# design.net
KiCad netlist of a schematic drawn in Altium Designer
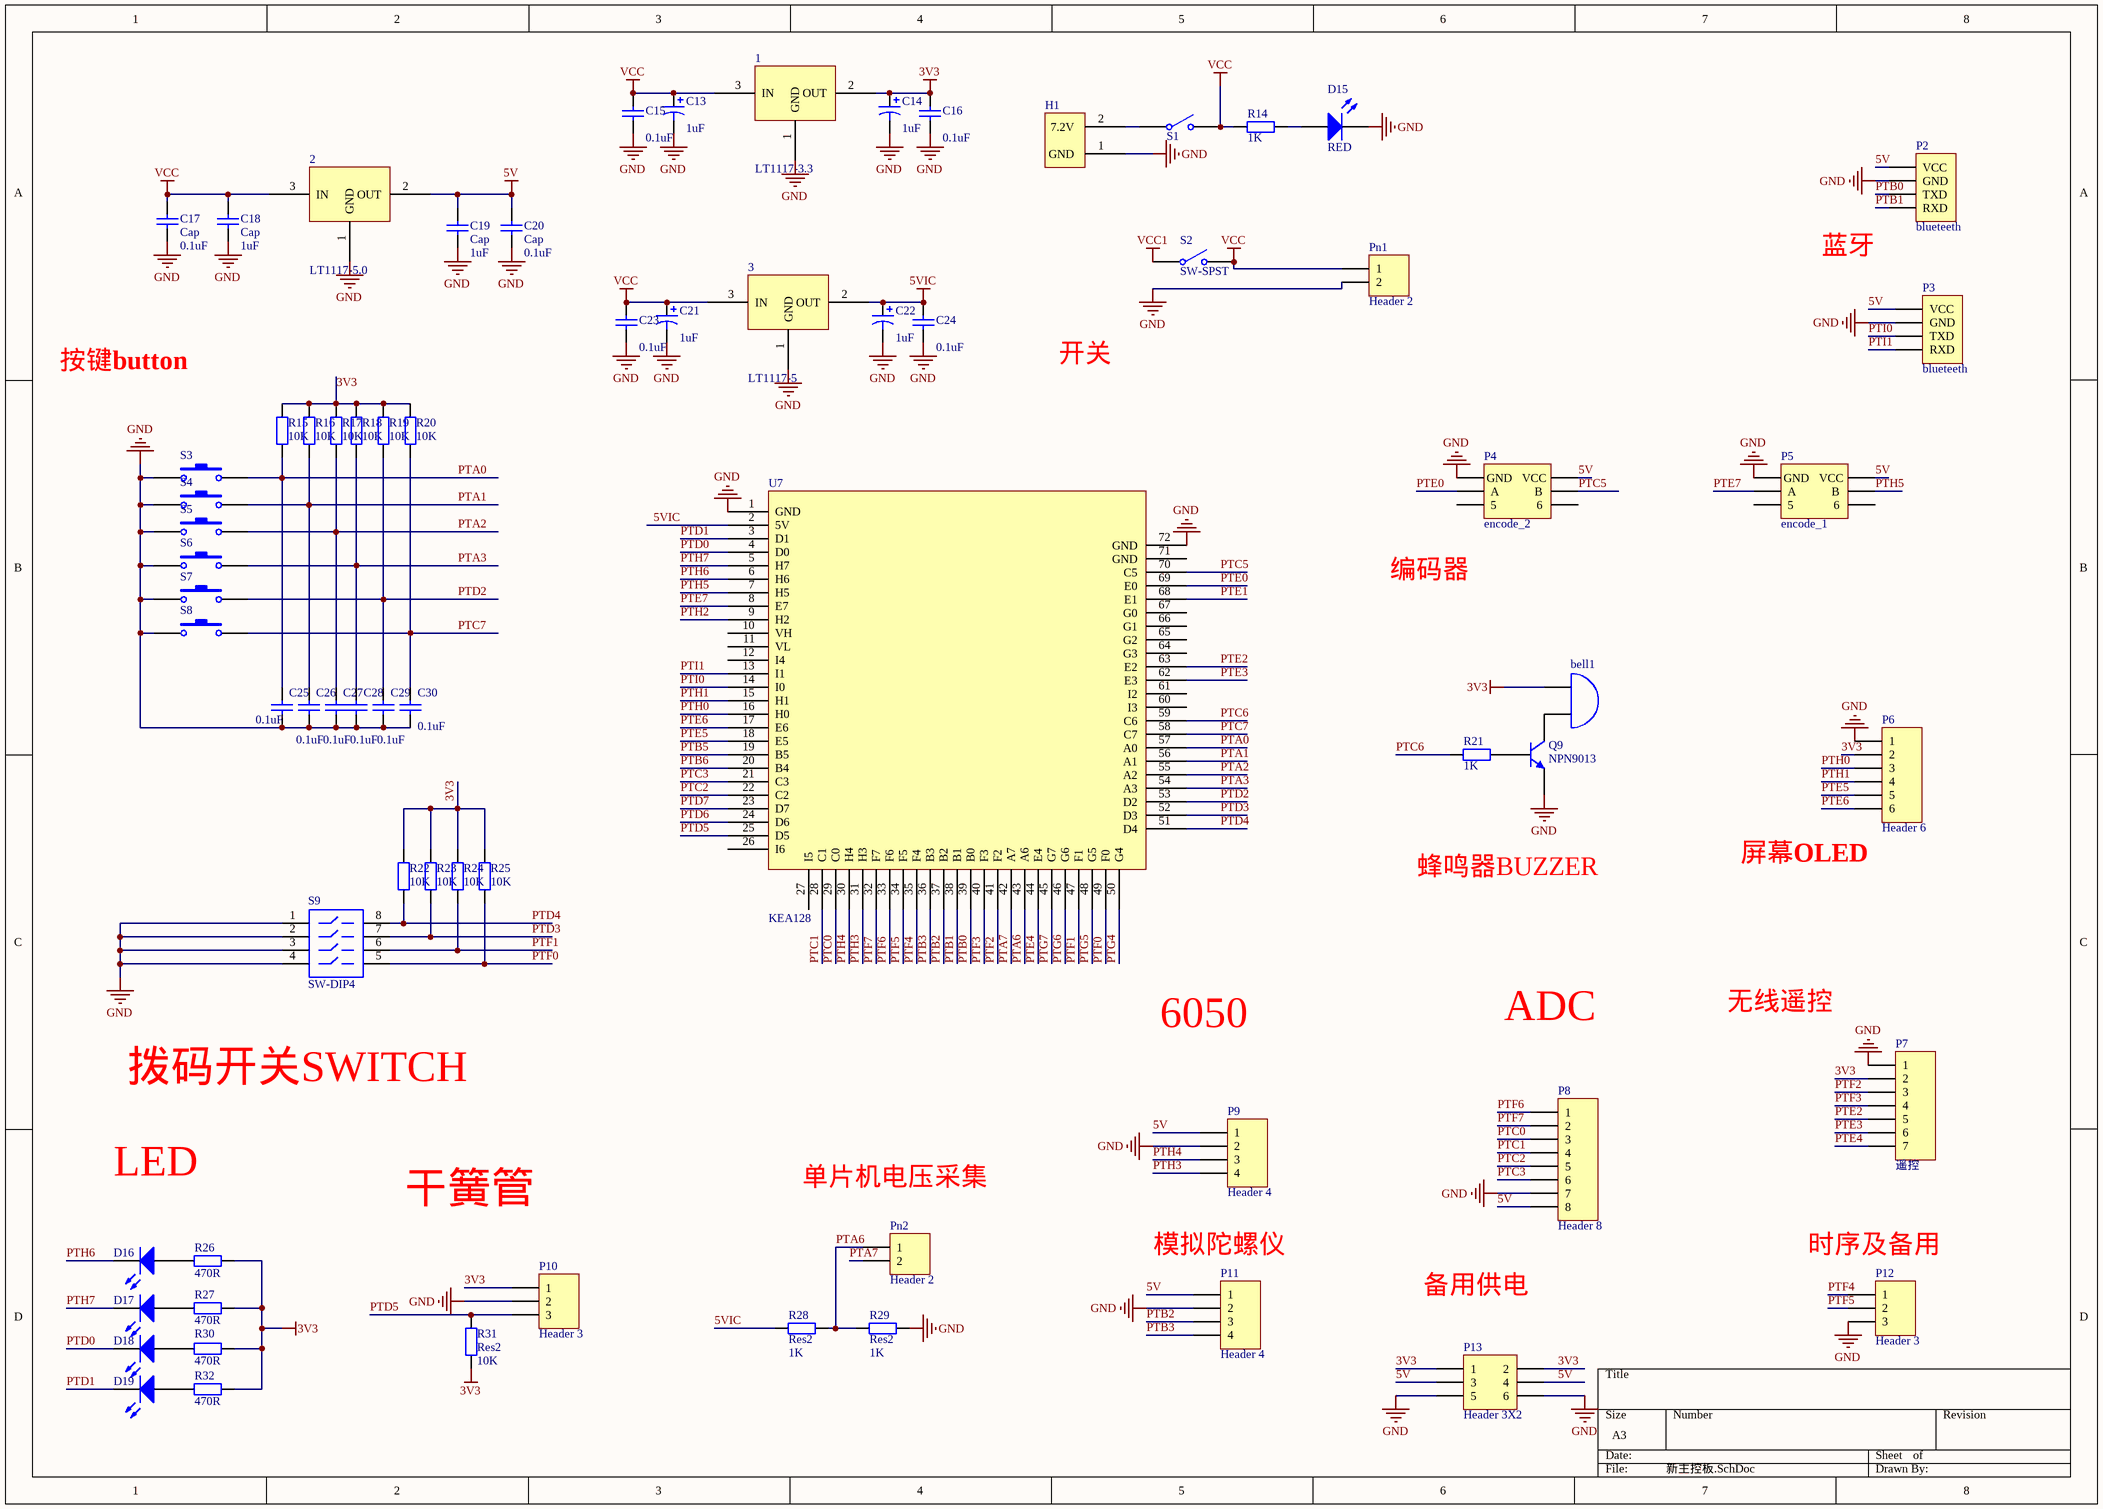
[diagram p0: 新主控板.SchDoc]

(export (version "E")
  (design (tool "Eeschema 10.0.6"))
  (components
    (comp (ref "1")
      (value "LT1117-3.3")
      (footprint "WH:1117")
      (libsource (lib "红牛板Schlib") (part "LT1117-3.3"))
    )
    (comp (ref "2") (value "LT1117-5.0") (footprint "WH:1117") (libsource (lib "新主控板") (part "LT1117-3.3")))
    (comp (ref "3")
      (value "LT1117-5")
      (footprint "WH:1117")
      (libsource (lib "红牛板Schlib") (part "LT1117-3.3"))
    )
    (comp (ref "bell1")
      (value "Bell")
      (footprint "470uF")
      (description "Electrical Bell")
      (fields (field (name "PUBLISHER") "Altium Limited"))
      (libsource (lib "Miscellaneous Devices") (part "Bell"))
    )
    (comp (ref "C13")
      (value "1uF")
      (footprint "0805(2012)")
      (description "Polarized Capacitor (Radial)")
      (fields (field (name "Comment") "Cap Pol1") (field (name "PUBLISHER") "Altium Limited"))
      (libsource (lib "Miscellaneous Devices") (part "Cap Pol1"))
    )
    (comp (ref "C14")
      (value "1uF")
      (footprint "0805(2012)")
      (description "Polarized Capacitor (Radial)")
      (fields (field (name "Comment") "Cap Pol1") (field (name "PUBLISHER") "Altium Limited"))
      (libsource (lib "Miscellaneous Devices") (part "Cap Pol1"))
    )
    (comp (ref "C15")
      (value "0.1uF")
      (footprint "0805(2012)")
      (description "Capacitor")
      (fields (field (name "Comment") "Cap") (field (name "PUBLISHER") "Altium Limited"))
      (libsource (lib "Miscellaneous Devices") (part "Cap"))
    )
    (comp (ref "C16")
      (value "0.1uF")
      (footprint "0805(2012)")
      (description "Capacitor")
      (fields (field (name "Comment") "Cap") (field (name "PUBLISHER") "Altium Limited"))
      (libsource (lib "Miscellaneous Devices") (part "Cap"))
    )
    (comp (ref "C17")
      (value "Cap")
      (footprint "0805(2012)")
      (description "Capacitor")
      (fields (field (name "ALTIUM_VALUE") "0.1uF") (field (name "PUBLISHER") "Altium Limited"))
      (libsource (lib "Miscellaneous Devices") (part "Cap"))
    )
    (comp (ref "C18")
      (value "Cap")
      (footprint "0805(2012)")
      (description "Capacitor")
      (fields (field (name "ALTIUM_VALUE") "1uF") (field (name "PUBLISHER") "Altium Limited"))
      (libsource (lib "Miscellaneous Devices") (part "Cap"))
    )
    (comp (ref "C19")
      (value "Cap")
      (footprint "0805(2012)")
      (description "Capacitor")
      (fields (field (name "ALTIUM_VALUE") "1uF") (field (name "PUBLISHER") "Altium Limited"))
      (libsource (lib "Miscellaneous Devices") (part "Cap"))
    )
    (comp (ref "C20")
      (value "Cap")
      (footprint "0805(2012)")
      (description "Capacitor")
      (fields (field (name "ALTIUM_VALUE") "0.1uF") (field (name "PUBLISHER") "Altium Limited"))
      (libsource (lib "Miscellaneous Devices") (part "Cap"))
    )
    (comp (ref "C21")
      (value "1uF")
      (footprint "0805(2012)")
      (description "Polarized Capacitor (Radial)")
      (fields (field (name "Comment") "Cap Pol1") (field (name "PUBLISHER") "Altium Limited"))
      (libsource (lib "Miscellaneous Devices") (part "Cap Pol1"))
    )
    (comp (ref "C22")
      (value "1uF")
      (footprint "0805(2012)")
      (description "Polarized Capacitor (Radial)")
      (fields (field (name "Comment") "Cap Pol1") (field (name "PUBLISHER") "Altium Limited"))
      (libsource (lib "Miscellaneous Devices") (part "Cap Pol1"))
    )
    (comp (ref "C23")
      (value "0.1uF")
      (footprint "0805(2012)")
      (description "Capacitor")
      (fields (field (name "Comment") "Cap") (field (name "PUBLISHER") "Altium Limited"))
      (libsource (lib "Miscellaneous Devices") (part "Cap"))
    )
    (comp (ref "C24")
      (value "0.1uF")
      (footprint "0805(2012)")
      (description "Capacitor")
      (fields (field (name "Comment") "Cap") (field (name "PUBLISHER") "Altium Limited"))
      (libsource (lib "Miscellaneous Devices") (part "Cap"))
    )
    (comp (ref "C25")
      (value "0.1uF")
      (footprint "0805(2012)")
      (description "Capacitor")
      (fields (field (name "Comment") "Cap") (field (name "PUBLISHER") "Altium Limited"))
      (libsource (lib "Miscellaneous Devices") (part "Cap"))
    )
    (comp (ref "C26")
      (value "0.1uF")
      (footprint "0805(2012)")
      (description "Capacitor")
      (fields (field (name "Comment") "Cap") (field (name "PUBLISHER") "Altium Limited"))
      (libsource (lib "Miscellaneous Devices") (part "Cap"))
    )
    (comp (ref "C27")
      (value "0.1uF")
      (footprint "0805(2012)")
      (description "Capacitor")
      (fields (field (name "Comment") "Cap") (field (name "PUBLISHER") "Altium Limited"))
      (libsource (lib "Miscellaneous Devices") (part "Cap"))
    )
    (comp (ref "C28")
      (value "0.1uF")
      (footprint "0805(2012)")
      (description "Capacitor")
      (fields (field (name "Comment") "Cap") (field (name "PUBLISHER") "Altium Limited"))
      (libsource (lib "Miscellaneous Devices") (part "Cap"))
    )
    (comp (ref "C29")
      (value "0.1uF")
      (footprint "0805(2012)")
      (description "Capacitor")
      (fields (field (name "Comment") "Cap") (field (name "PUBLISHER") "Altium Limited"))
      (libsource (lib "Miscellaneous Devices") (part "Cap"))
    )
    (comp (ref "C30")
      (value "0.1uF")
      (footprint "0805(2012)")
      (description "Capacitor")
      (fields (field (name "Comment") "Cap") (field (name "PUBLISHER") "Altium Limited"))
      (libsource (lib "Miscellaneous Devices") (part "Cap"))
    )
    (comp (ref "D15")
      (value "RED")
      (footprint "0805LED")
      (description "Typical RED, GREEN, YELLOW, AMBER GaAs LED")
      (fields (field (name "PUBLISHER") "Altium Limited"))
      (libsource (lib "MOS motor driving module ") (part "LED2"))
    )
    (comp (ref "D16")
      (value "LED0")
      (footprint "0805LED")
      (description "Typical INFRARED GaAs LED")
      (fields (field (name "PUBLISHER") "Altium Limited"))
      (libsource (lib "Miscellaneous Devices") (part "LED0"))
    )
    (comp (ref "D17")
      (value "LED0")
      (footprint "0805LED")
      (description "Typical INFRARED GaAs LED")
      (fields (field (name "PUBLISHER") "Altium Limited"))
      (libsource (lib "Miscellaneous Devices") (part "LED0"))
    )
    (comp (ref "D18")
      (value "LED0")
      (footprint "0805LED")
      (description "Typical INFRARED GaAs LED")
      (fields (field (name "PUBLISHER") "Altium Limited"))
      (libsource (lib "Miscellaneous Devices") (part "LED0"))
    )
    (comp (ref "D19")
      (value "LED0")
      (footprint "0805LED")
      (description "Typical INFRARED GaAs LED")
      (fields (field (name "PUBLISHER") "Altium Limited"))
      (libsource (lib "Miscellaneous Devices") (part "LED0"))
    )
    (comp (ref "H1") (value "H1") (footprint "KF301-2P") (libsource (lib "主控板原理图库") (part "H1")))
    (comp (ref "P2") (value "blueteeth") (footprint "HDR1X4") (libsource (lib "总原理图库") (part "blueteeth")))
    (comp (ref "P3") (value "blueteeth") (footprint "HDR1X4") (libsource (lib "新主控板") (part "blueteeth")))
    (comp (ref "P4") (value "encode_2") (footprint "HDR2X3") (libsource (lib "总原理图库") (part "encode")))
    (comp (ref "P5") (value "encode_1") (footprint "HDR2X3") (libsource (lib "总原理图库") (part "encode")))
    (comp (ref "P6")
      (value "Header 6")
      (footprint "HDR1X6")
      (description "Header, 6-Pin")
      (fields (field (name "PUBLISHER") "Altium Limited"))
      (libsource (lib "Miscellaneous Connectors") (part "Header 6"))
    )
    (comp (ref "P7")
      (value "遥控")
      (footprint "HDR1X7")
      (description "Header, 7-Pin")
      (fields (field (name "PUBLISHER") "Altium Limited"))
      (libsource (lib "Miscellaneous Connectors") (part "MHDR1X7"))
    )
    (comp (ref "P8")
      (value "Header 8")
      (footprint "HDR1X8")
      (description "Header, 8-Pin")
      (fields (field (name "PUBLISHER") "Altium Limited"))
      (libsource (lib "Miscellaneous Connectors") (part "Header 8"))
    )
    (comp (ref "P9")
      (value "Header 4")
      (footprint "HDR1X4")
      (description "Header, 4-Pin")
      (fields (field (name "PUBLISHER") "Altium Limited"))
      (libsource (lib "Miscellaneous Connectors") (part "Header 4"))
    )
    (comp (ref "P10")
      (value "Header 3")
      (footprint "HDR1X3")
      (description "Header, 3-Pin")
      (fields (field (name "PUBLISHER") "Altium Limited"))
      (libsource (lib "Miscellaneous Connectors") (part "Header 3"))
    )
    (comp (ref "P11")
      (value "Header 4")
      (footprint "HDR1X4")
      (description "Header, 4-Pin")
      (fields (field (name "PUBLISHER") "Altium Limited"))
      (libsource (lib "Miscellaneous Connectors") (part "Header 4"))
    )
    (comp (ref "P12")
      (value "Header 3")
      (footprint "HDR1X3")
      (description "Header, 3-Pin")
      (fields (field (name "PUBLISHER") "Altium Limited"))
      (libsource (lib "新主控板") (part "Header 3"))
    )
    (comp (ref "P13")
      (value "Header 3X2")
      (footprint "HDR2X3")
      (description "Header, 3-Pin, Dual row")
      (fields (field (name "PUBLISHER") "Altium Limited"))
      (libsource (lib "Miscellaneous Connectors") (part "Header 3X2"))
    )
    (comp (ref "Pn1")
      (value "Header 2")
      (footprint "HDR1X2")
      (description "Header, 2-Pin")
      (fields (field (name "PUBLISHER") "Altium Limited"))
      (libsource (lib "Miscellaneous Connectors") (part "Header 2"))
    )
    (comp (ref "Pn2")
      (value "Header 2")
      (footprint "HDR1X2")
      (description "Header, 2-Pin")
      (fields (field (name "PUBLISHER") "Altium Limited"))
      (libsource (lib "新主控板") (part "Header 2"))
    )
    (comp (ref "Q9")
      (value "NPN9013")
      (footprint "TO-226-AE")
      (description "NPN General Purpose Amplifier")
      (fields (field (name "PUBLISHER") "Altium Limited"))
      (libsource (lib "Miscellaneous Devices") (part "2N3904"))
    )
    (comp (ref "R14")
      (value "1K")
      (footprint "0805(2012)")
      (description "Resistor")
      (fields (field (name "Comment") "Res2") (field (name "PUBLISHER") "Altium Limited"))
      (libsource (lib "") (part "Res2_1"))
    )
    (comp (ref "R15")
      (value "10K")
      (footprint "0805(2012)")
      (description "Resistor")
      (fields (field (name "Comment") "Res2") (field (name "PUBLISHER") "Altium Limited"))
      (libsource (lib "MOS motor driving module ") (part "Res2"))
    )
    (comp (ref "R16")
      (value "10K")
      (footprint "0805(2012)")
      (description "Resistor")
      (fields (field (name "Comment") "Res2") (field (name "PUBLISHER") "Altium Limited"))
      (libsource (lib "MOS motor driving module ") (part "Res2"))
    )
    (comp (ref "R17")
      (value "10K")
      (footprint "0805(2012)")
      (description "Resistor")
      (fields (field (name "Comment") "Res2") (field (name "PUBLISHER") "Altium Limited"))
      (libsource (lib "MOS motor driving module ") (part "Res2"))
    )
    (comp (ref "R18")
      (value "10K")
      (footprint "0805(2012)")
      (description "Resistor")
      (fields (field (name "Comment") "Res2") (field (name "PUBLISHER") "Altium Limited"))
      (libsource (lib "MOS motor driving module ") (part "Res2"))
    )
    (comp (ref "R19")
      (value "10K")
      (footprint "0805(2012)")
      (description "Resistor")
      (fields (field (name "Comment") "Res2") (field (name "PUBLISHER") "Altium Limited"))
      (libsource (lib "MOS motor driving module ") (part "Res2"))
    )
    (comp (ref "R20")
      (value "10K")
      (footprint "0805(2012)")
      (description "Resistor")
      (fields (field (name "Comment") "Res2") (field (name "PUBLISHER") "Altium Limited"))
      (libsource (lib "MOS motor driving module ") (part "Res2"))
    )
    (comp (ref "R21")
      (value "1K")
      (footprint "0805(2012)")
      (description "Resistor")
      (fields (field (name "Comment") "Res2") (field (name "PUBLISHER") "Altium Limited"))
      (libsource (lib "主控板原理图") (part "Res2"))
    )
    (comp (ref "R22")
      (value "10K")
      (footprint "0805(2012)")
      (description "Resistor")
      (fields (field (name "Comment") "Res2") (field (name "PUBLISHER") "Altium Limited"))
      (libsource (lib "MOS motor driving module ") (part "Res2"))
    )
    (comp (ref "R23")
      (value "10K")
      (footprint "0805(2012)")
      (description "Resistor")
      (fields (field (name "Comment") "Res2") (field (name "PUBLISHER") "Altium Limited"))
      (libsource (lib "MOS motor driving module ") (part "Res2"))
    )
    (comp (ref "R24")
      (value "10K")
      (footprint "0805(2012)")
      (description "Resistor")
      (fields (field (name "Comment") "Res2") (field (name "PUBLISHER") "Altium Limited"))
      (libsource (lib "MOS motor driving module ") (part "Res2"))
    )
    (comp (ref "R25")
      (value "10K")
      (footprint "0805(2012)")
      (description "Resistor")
      (fields (field (name "Comment") "Res2") (field (name "PUBLISHER") "Altium Limited"))
      (libsource (lib "MOS motor driving module ") (part "Res2"))
    )
    (comp (ref "R26")
      (value "470R")
      (footprint "0805(2012)")
      (description "Resistor")
      (fields (field (name "Comment") "Res2") (field (name "PUBLISHER") "Altium Limited"))
      (libsource (lib "Miscellaneous Devices") (part "Res2"))
    )
    (comp (ref "R27")
      (value "470R")
      (footprint "0805(2012)")
      (description "Resistor")
      (fields (field (name "Comment") "Res2") (field (name "PUBLISHER") "Altium Limited"))
      (libsource (lib "Miscellaneous Devices") (part "Res2"))
    )
    (comp (ref "R28")
      (value "Res2")
      (footprint "0805(2012)")
      (description "Resistor")
      (fields (field (name "ALTIUM_VALUE") "1K") (field (name "PUBLISHER") "Altium Limited"))
      (libsource (lib "Miscellaneous Devices") (part "Res2"))
    )
    (comp (ref "R29")
      (value "Res2")
      (footprint "0805(2012)")
      (description "Resistor")
      (fields (field (name "ALTIUM_VALUE") "1K") (field (name "PUBLISHER") "Altium Limited"))
      (libsource (lib "Miscellaneous Devices") (part "Res2"))
    )
    (comp (ref "R30")
      (value "470R")
      (footprint "0805(2012)")
      (description "Resistor")
      (fields (field (name "Comment") "Res2") (field (name "PUBLISHER") "Altium Limited"))
      (libsource (lib "Miscellaneous Devices") (part "Res2"))
    )
    (comp (ref "R31")
      (value "Res2")
      (footprint "0805(2012)")
      (description "Resistor")
      (fields (field (name "ALTIUM_VALUE") "10K") (field (name "PUBLISHER") "Altium Limited"))
      (libsource (lib "") (part "Res2_1"))
    )
    (comp (ref "R32")
      (value "470R")
      (footprint "0805(2012)")
      (description "Resistor")
      (fields (field (name "Comment") "Res2") (field (name "PUBLISHER") "Altium Limited"))
      (libsource (lib "Miscellaneous Devices") (part "Res2"))
    )
    (comp (ref "S1")
      (value "SW-SPST")
      (footprint "SWICH_3")
      (description "Single-Pole, Single-Throw Switch")
      (fields (field (name "PUBLISHER") "Altium Limited"))
      (libsource (lib "总原理图库") (part "SW-SPST"))
    )
    (comp (ref "S2")
      (value "SW-SPST")
      (footprint "SWICH_3")
      (description "Single-Pole, Single-Throw Switch")
      (fields (field (name "PUBLISHER") "Altium Limited"))
      (libsource (lib "Miscellaneous Devices") (part "SW-SPST"))
    )
    (comp (ref "S3")
      (value "SW-PB")
      (footprint "PCBComponent_1")
      (description "Switch")
      (fields (field (name "PUBLISHER") "Altium Limited"))
      (libsource (lib "Miscellaneous Devices") (part "SW-PB"))
    )
    (comp (ref "S4")
      (value "SW-PB")
      (footprint "PCBComponent_1")
      (description "Switch")
      (fields (field (name "PUBLISHER") "Altium Limited"))
      (libsource (lib "Miscellaneous Devices") (part "SW-PB"))
    )
    (comp (ref "S5")
      (value "SW-PB")
      (footprint "PCBComponent_1")
      (description "Switch")
      (fields (field (name "PUBLISHER") "Altium Limited"))
      (libsource (lib "Miscellaneous Devices") (part "SW-PB"))
    )
    (comp (ref "S6")
      (value "SW-PB")
      (footprint "PCBComponent_1")
      (description "Switch")
      (fields (field (name "PUBLISHER") "Altium Limited"))
      (libsource (lib "Miscellaneous Devices") (part "SW-PB"))
    )
    (comp (ref "S7")
      (value "SW-PB")
      (footprint "PCBComponent_1")
      (description "Switch")
      (fields (field (name "PUBLISHER") "Altium Limited"))
      (libsource (lib "Miscellaneous Devices") (part "SW-PB"))
    )
    (comp (ref "S8")
      (value "SW-PB")
      (footprint "PCBComponent_1")
      (description "Switch")
      (fields (field (name "PUBLISHER") "Altium Limited"))
      (libsource (lib "Miscellaneous Devices") (part "SW-PB"))
    )
    (comp (ref "S9")
      (value "SW-DIP4")
      (footprint "DIP-8")
      (description "DIP Switch")
      (fields (field (name "PUBLISHER") "Altium Limited"))
      (libsource (lib "总原理图库") (part "SW-DIP4"))
    )
    (comp (ref "U7") (value "KEA128") (footprint "KEA128_BOARD") (libsource (lib "KEA128") (part "KEA128")))
  )
  (nets
    (net (code "1") (name "/PTA0") (class "Default")
      (node (ref "C25") (pin "2") (pinfunction "2_2") (pintype "passive"))
      (node (ref "R15") (pin "1") (pinfunction "1_1") (pintype "passive"))
      (node (ref "S3") (pin "2") (pinfunction "2_2") (pintype "passive"))
      (node (ref "U7") (pin "57") (pinfunction "A0_57") (pintype "passive"))
    )
    (net (code "2") (name "/PTA1") (class "Default")
      (node (ref "C26") (pin "2") (pinfunction "2_2") (pintype "passive"))
      (node (ref "R16") (pin "1") (pinfunction "1_1") (pintype "passive"))
      (node (ref "S4") (pin "2") (pinfunction "2_2") (pintype "passive"))
      (node (ref "U7") (pin "56") (pinfunction "A1_56") (pintype "passive"))
    )
    (net (code "3") (name "/PTA2") (class "Default")
      (node (ref "C27") (pin "2") (pinfunction "2_2") (pintype "passive"))
      (node (ref "R17") (pin "1") (pinfunction "1_1") (pintype "passive"))
      (node (ref "S5") (pin "2") (pinfunction "2_2") (pintype "passive"))
      (node (ref "U7") (pin "55") (pinfunction "A2_55") (pintype "passive"))
    )
    (net (code "4") (name "/PTA3") (class "Default")
      (node (ref "C28") (pin "2") (pinfunction "2_2") (pintype "passive"))
      (node (ref "R18") (pin "1") (pinfunction "1_1") (pintype "passive"))
      (node (ref "S6") (pin "2") (pinfunction "2_2") (pintype "passive"))
      (node (ref "U7") (pin "54") (pinfunction "A3_54") (pintype "passive"))
    )
    (net (code "5") (name "/PTA6") (class "Default")
      (node (ref "Pn2") (pin "1") (pinfunction "1_1") (pintype "passive"))
      (node (ref "R28") (pin "2") (pinfunction "2_2") (pintype "passive"))
      (node (ref "R29") (pin "1") (pinfunction "1_1") (pintype "passive"))
      (node (ref "U7") (pin "43") (pinfunction "A6_43") (pintype "passive"))
    )
    (net (code "6") (name "/PTA7") (class "Default")
      (node (ref "Pn2") (pin "2") (pinfunction "2_2") (pintype "passive"))
      (node (ref "U7") (pin "42") (pinfunction "A7_42") (pintype "passive"))
    )
    (net (code "7") (name "/PTB0") (class "Default")
      (node (ref "P2") (pin "3") (pinfunction "TXD_3") (pintype "passive"))
      (node (ref "U7") (pin "39") (pinfunction "B0_39") (pintype "passive"))
    )
    (net (code "8") (name "/PTB1") (class "Default")
      (node (ref "P2") (pin "4") (pinfunction "RXD_4") (pintype "passive"))
      (node (ref "U7") (pin "38") (pinfunction "B1_38") (pintype "passive"))
    )
    (net (code "9") (name "/PTB2") (class "Default")
      (node (ref "P11") (pin "3") (pinfunction "3_3") (pintype "passive"))
      (node (ref "U7") (pin "37") (pinfunction "B2_37") (pintype "passive"))
    )
    (net (code "10") (name "/PTB3") (class "Default")
      (node (ref "P11") (pin "4") (pinfunction "4_4") (pintype "passive"))
      (node (ref "U7") (pin "36") (pinfunction "B3_36") (pintype "passive"))
    )
    (net (code "11") (name "/PTB5") (class "Default")
      (node (ref "U7") (pin "19") (pinfunction "B5_19") (pintype "passive"))
    )
    (net (code "12") (name "/PTB6") (class "Default")
      (node (ref "U7") (pin "20") (pinfunction "B4_20") (pintype "passive"))
    )
    (net (code "13") (name "/PTC0") (class "Default")
      (node (ref "P8") (pin "3") (pinfunction "3_3") (pintype "passive"))
      (node (ref "U7") (pin "29") (pinfunction "C0_29") (pintype "passive"))
    )
    (net (code "14") (name "/PTC1") (class "Default")
      (node (ref "P8") (pin "4") (pinfunction "4_4") (pintype "passive"))
      (node (ref "U7") (pin "28") (pinfunction "C1_28") (pintype "passive"))
    )
    (net (code "15") (name "/PTC2") (class "Default")
      (node (ref "P8") (pin "5") (pinfunction "5_5") (pintype "passive"))
      (node (ref "U7") (pin "22") (pinfunction "C2_22") (pintype "passive"))
    )
    (net (code "16") (name "/PTC3") (class "Default")
      (node (ref "P8") (pin "6") (pinfunction "6_6") (pintype "passive"))
      (node (ref "U7") (pin "21") (pinfunction "C3_21") (pintype "passive"))
    )
    (net (code "17") (name "/PTC5") (class "Default")
      (node (ref "P4") (pin "4") (pinfunction "B_4") (pintype "passive"))
      (node (ref "U7") (pin "70") (pinfunction "C5_70") (pintype "passive"))
    )
    (net (code "18") (name "/PTC6") (class "Default")
      (node (ref "R21") (pin "1") (pinfunction "1_1") (pintype "passive"))
      (node (ref "U7") (pin "59") (pinfunction "C6_59") (pintype "passive"))
    )
    (net (code "19") (name "/PTC7") (class "Default")
      (node (ref "C30") (pin "2") (pinfunction "2_2") (pintype "passive"))
      (node (ref "R20") (pin "1") (pinfunction "1_1") (pintype "passive"))
      (node (ref "S8") (pin "2") (pinfunction "2_2") (pintype "passive"))
      (node (ref "U7") (pin "58") (pinfunction "C7_58") (pintype "passive"))
    )
    (net (code "20") (name "/PTD0") (class "Default")
      (node (ref "D18") (pin "2") (pinfunction "K_2") (pintype "passive"))
      (node (ref "U7") (pin "4") (pinfunction "D0_4") (pintype "passive"))
    )
    (net (code "21") (name "/PTD1") (class "Default")
      (node (ref "D19") (pin "2") (pinfunction "K_2") (pintype "passive"))
      (node (ref "U7") (pin "3") (pinfunction "D1_3") (pintype "passive"))
    )
    (net (code "22") (name "/PTD2") (class "Default")
      (node (ref "C29") (pin "2") (pinfunction "2_2") (pintype "passive"))
      (node (ref "R19") (pin "1") (pinfunction "1_1") (pintype "passive"))
      (node (ref "S7") (pin "2") (pinfunction "2_2") (pintype "passive"))
      (node (ref "U7") (pin "53") (pinfunction "D2_53") (pintype "passive"))
    )
    (net (code "23") (name "/PTD3") (class "Default")
      (node (ref "R23") (pin "1") (pinfunction "1_1") (pintype "passive"))
      (node (ref "S9") (pin "7") (pinfunction "7_7") (pintype "passive"))
      (node (ref "U7") (pin "52") (pinfunction "D3_52") (pintype "passive"))
    )
    (net (code "24") (name "/PTD4") (class "Default")
      (node (ref "R22") (pin "1") (pinfunction "1_1") (pintype "passive"))
      (node (ref "S9") (pin "8") (pinfunction "8_8") (pintype "passive"))
      (node (ref "U7") (pin "51") (pinfunction "D4_51") (pintype "passive"))
    )
    (net (code "25") (name "/PTD5") (class "Default")
      (node (ref "P10") (pin "3") (pinfunction "3_3") (pintype "passive"))
      (node (ref "R31") (pin "2") (pinfunction "2_2") (pintype "passive"))
      (node (ref "U7") (pin "25") (pinfunction "D5_25") (pintype "passive"))
    )
    (net (code "26") (name "/PTD6") (class "Default")
      (node (ref "U7") (pin "24") (pinfunction "D6_24") (pintype "passive"))
    )
    (net (code "27") (name "/PTD7") (class "Default")
      (node (ref "U7") (pin "23") (pinfunction "D7_23") (pintype "passive"))
    )
    (net (code "28") (name "/PTE0") (class "Default")
      (node (ref "P4") (pin "3") (pinfunction "A_3") (pintype "passive"))
      (node (ref "U7") (pin "69") (pinfunction "E0_69") (pintype "passive"))
    )
    (net (code "29") (name "/PTE1") (class "Default")
      (node (ref "U7") (pin "68") (pinfunction "E1_68") (pintype "passive"))
    )
    (net (code "30") (name "/PTE2") (class "Default")
      (node (ref "P7") (pin "5") (pinfunction "5_5") (pintype "passive"))
      (node (ref "U7") (pin "63") (pinfunction "E2_63") (pintype "passive"))
    )
    (net (code "31") (name "/PTE3") (class "Default")
      (node (ref "P7") (pin "6") (pinfunction "6_6") (pintype "passive"))
      (node (ref "U7") (pin "62") (pinfunction "E3_62") (pintype "passive"))
    )
    (net (code "32") (name "/PTE4") (class "Default")
      (node (ref "P7") (pin "7") (pinfunction "7_7") (pintype "passive"))
      (node (ref "U7") (pin "44") (pinfunction "E4_44") (pintype "passive"))
    )
    (net (code "33") (name "/PTE5") (class "Default")
      (node (ref "P6") (pin "5") (pinfunction "5_5") (pintype "passive"))
      (node (ref "U7") (pin "18") (pinfunction "E5_18") (pintype "passive"))
    )
    (net (code "34") (name "/PTE6") (class "Default")
      (node (ref "P6") (pin "6") (pinfunction "6_6") (pintype "passive"))
      (node (ref "U7") (pin "17") (pinfunction "E6_17") (pintype "passive"))
    )
    (net (code "35") (name "/PTE7") (class "Default")
      (node (ref "P5") (pin "3") (pinfunction "A_3") (pintype "passive"))
      (node (ref "U7") (pin "8") (pinfunction "E7_8") (pintype "passive"))
    )
    (net (code "36") (name "/PTF0") (class "Default")
      (node (ref "R25") (pin "1") (pinfunction "1_1") (pintype "passive"))
      (node (ref "S9") (pin "5") (pinfunction "5_5") (pintype "passive"))
      (node (ref "U7") (pin "49") (pinfunction "F0_49") (pintype "passive"))
    )
    (net (code "37") (name "/PTF1") (class "Default")
      (node (ref "R24") (pin "1") (pinfunction "1_1") (pintype "passive"))
      (node (ref "S9") (pin "6") (pinfunction "6_6") (pintype "passive"))
      (node (ref "U7") (pin "47") (pinfunction "F1_47") (pintype "passive"))
    )
    (net (code "38") (name "/PTF2") (class "Default")
      (node (ref "P7") (pin "3") (pinfunction "3_3") (pintype "passive"))
      (node (ref "U7") (pin "41") (pinfunction "F2_41") (pintype "passive"))
    )
    (net (code "39") (name "/PTF3") (class "Default")
      (node (ref "P7") (pin "4") (pinfunction "4_4") (pintype "passive"))
      (node (ref "U7") (pin "40") (pinfunction "F3_40") (pintype "passive"))
    )
    (net (code "40") (name "/PTF4") (class "Default")
      (node (ref "P12") (pin "1") (pinfunction "1_1") (pintype "passive"))
      (node (ref "U7") (pin "35") (pinfunction "F4_35") (pintype "passive"))
    )
    (net (code "41") (name "/PTF5") (class "Default")
      (node (ref "P12") (pin "2") (pinfunction "2_2") (pintype "passive"))
      (node (ref "U7") (pin "34") (pinfunction "F5_34") (pintype "passive"))
    )
    (net (code "42") (name "/PTF6") (class "Default")
      (node (ref "P8") (pin "1") (pinfunction "1_1") (pintype "passive"))
      (node (ref "U7") (pin "33") (pinfunction "F6_33") (pintype "passive"))
    )
    (net (code "43") (name "/PTF7") (class "Default")
      (node (ref "P8") (pin "2") (pinfunction "2_2") (pintype "passive"))
      (node (ref "U7") (pin "32") (pinfunction "F7_32") (pintype "passive"))
    )
    (net (code "44") (name "/PTG4") (class "Default")
      (node (ref "U7") (pin "50") (pinfunction "G4_50") (pintype "passive"))
    )
    (net (code "45") (name "/PTG5") (class "Default")
      (node (ref "U7") (pin "48") (pinfunction "G5_48") (pintype "passive"))
    )
    (net (code "46") (name "/PTG6") (class "Default")
      (node (ref "U7") (pin "46") (pinfunction "G6_46") (pintype "passive"))
    )
    (net (code "47") (name "/PTG7") (class "Default")
      (node (ref "U7") (pin "45") (pinfunction "G7_45") (pintype "passive"))
    )
    (net (code "48") (name "/PTH0") (class "Default")
      (node (ref "P6") (pin "3") (pinfunction "3_3") (pintype "passive"))
      (node (ref "U7") (pin "16") (pinfunction "H0_16") (pintype "passive"))
    )
    (net (code "49") (name "/PTH1") (class "Default")
      (node (ref "P6") (pin "4") (pinfunction "4_4") (pintype "passive"))
      (node (ref "U7") (pin "15") (pinfunction "H1_15") (pintype "passive"))
    )
    (net (code "50") (name "/PTH2") (class "Default")
      (node (ref "U7") (pin "9") (pinfunction "H2_9") (pintype "passive"))
    )
    (net (code "51") (name "/PTH3") (class "Default")
      (node (ref "P9") (pin "4") (pinfunction "4_4") (pintype "passive"))
      (node (ref "U7") (pin "31") (pinfunction "H3_31") (pintype "passive"))
    )
    (net (code "52") (name "/PTH4") (class "Default")
      (node (ref "P9") (pin "3") (pinfunction "3_3") (pintype "passive"))
      (node (ref "U7") (pin "30") (pinfunction "H4_30") (pintype "passive"))
    )
    (net (code "53") (name "/PTH5") (class "Default")
      (node (ref "P5") (pin "4") (pinfunction "B_4") (pintype "passive"))
      (node (ref "U7") (pin "7") (pinfunction "H5_7") (pintype "passive"))
    )
    (net (code "54") (name "/PTH6") (class "Default")
      (node (ref "D16") (pin "2") (pinfunction "K_2") (pintype "passive"))
      (node (ref "U7") (pin "6") (pinfunction "H6_6") (pintype "passive"))
    )
    (net (code "55") (name "/PTH7") (class "Default")
      (node (ref "D17") (pin "2") (pinfunction "K_2") (pintype "passive"))
      (node (ref "U7") (pin "5") (pinfunction "H7_5") (pintype "passive"))
    )
    (net (code "56") (name "/PTI0") (class "Default")
      (node (ref "P3") (pin "3") (pinfunction "TXD_3") (pintype "passive"))
      (node (ref "U7") (pin "14") (pinfunction "I0_14") (pintype "passive"))
    )
    (net (code "57") (name "/PTI1") (class "Default")
      (node (ref "P3") (pin "4") (pinfunction "RXD_4") (pintype "passive"))
      (node (ref "U7") (pin "13") (pinfunction "I1_13") (pintype "passive"))
    )
    (net (code "58") (name "3V3") (class "Default")
      (node (ref "1") (pin "2") (pinfunction "OUT_2") (pintype "open_emitter"))
      (node (ref "C14") (pin "1") (pinfunction "1_1") (pintype "passive"))
      (node (ref "C16") (pin "2") (pinfunction "2_2") (pintype "passive"))
      (node (ref "P10") (pin "1") (pinfunction "1_1") (pintype "passive"))
      (node (ref "P13") (pin "1") (pinfunction "1_1") (pintype "passive"))
      (node (ref "P13") (pin "2") (pinfunction "2_2") (pintype "passive"))
      (node (ref "P6") (pin "2") (pinfunction "2_2") (pintype "passive"))
      (node (ref "P7") (pin "2") (pinfunction "2_2") (pintype "passive"))
      (node (ref "R15") (pin "2") (pinfunction "2_2") (pintype "passive"))
      (node (ref "R16") (pin "2") (pinfunction "2_2") (pintype "passive"))
      (node (ref "R17") (pin "2") (pinfunction "2_2") (pintype "passive"))
      (node (ref "R18") (pin "2") (pinfunction "2_2") (pintype "passive"))
      (node (ref "R19") (pin "2") (pinfunction "2_2") (pintype "passive"))
      (node (ref "R20") (pin "2") (pinfunction "2_2") (pintype "passive"))
      (node (ref "R22") (pin "2") (pinfunction "2_2") (pintype "passive"))
      (node (ref "R23") (pin "2") (pinfunction "2_2") (pintype "passive"))
      (node (ref "R24") (pin "2") (pinfunction "2_2") (pintype "passive"))
      (node (ref "R25") (pin "2") (pinfunction "2_2") (pintype "passive"))
      (node (ref "R26") (pin "2") (pinfunction "2_2") (pintype "passive"))
      (node (ref "R27") (pin "2") (pinfunction "2_2") (pintype "passive"))
      (node (ref "R30") (pin "2") (pinfunction "2_2") (pintype "passive"))
      (node (ref "R31") (pin "1") (pinfunction "1_1") (pintype "passive"))
      (node (ref "R32") (pin "2") (pinfunction "2_2") (pintype "passive"))
      (node (ref "bell1") (pin "1") (pinfunction "A_1") (pintype "passive"))
    )
    (net (code "59") (name "5V") (class "Default")
      (node (ref "2") (pin "2") (pinfunction "OUT_2") (pintype "open_emitter"))
      (node (ref "C19") (pin "2") (pinfunction "2_2") (pintype "passive"))
      (node (ref "C20") (pin "2") (pinfunction "2_2") (pintype "passive"))
      (node (ref "P11") (pin "1") (pinfunction "1_1") (pintype "passive"))
      (node (ref "P13") (pin "3") (pinfunction "3_3") (pintype "passive"))
      (node (ref "P13") (pin "4") (pinfunction "4_4") (pintype "passive"))
      (node (ref "P2") (pin "1") (pinfunction "VCC_1") (pintype "passive"))
      (node (ref "P3") (pin "1") (pinfunction "VCC_1") (pintype "passive"))
      (node (ref "P4") (pin "2") (pinfunction "VCC_2") (pintype "passive"))
      (node (ref "P5") (pin "2") (pinfunction "VCC_2") (pintype "passive"))
      (node (ref "P8") (pin "8") (pinfunction "8_8") (pintype "passive"))
      (node (ref "P9") (pin "1") (pinfunction "1_1") (pintype "passive"))
    )
    (net (code "60") (name "5VIC") (class "Default")
      (node (ref "3") (pin "2") (pinfunction "OUT_2") (pintype "open_emitter"))
      (node (ref "C22") (pin "1") (pinfunction "1_1") (pintype "passive"))
      (node (ref "C24") (pin "2") (pinfunction "2_2") (pintype "passive"))
      (node (ref "R28") (pin "1") (pinfunction "1_1") (pintype "passive"))
      (node (ref "U7") (pin "2") (pinfunction "5V_2") (pintype "passive"))
    )
    (net (code "61") (name "GND") (class "Default")
      (node (ref "1") (pin "1") (pinfunction "GND_1") (pintype "open_emitter"))
      (node (ref "2") (pin "1") (pinfunction "GND_1") (pintype "open_emitter"))
      (node (ref "3") (pin "1") (pinfunction "GND_1") (pintype "open_emitter"))
      (node (ref "C13") (pin "2") (pinfunction "2_2") (pintype "passive"))
      (node (ref "C14") (pin "2") (pinfunction "2_2") (pintype "passive"))
      (node (ref "C15") (pin "1") (pinfunction "1_1") (pintype "passive"))
      (node (ref "C16") (pin "1") (pinfunction "1_1") (pintype "passive"))
      (node (ref "C17") (pin "1") (pinfunction "1_1") (pintype "passive"))
      (node (ref "C18") (pin "1") (pinfunction "1_1") (pintype "passive"))
      (node (ref "C19") (pin "1") (pinfunction "1_1") (pintype "passive"))
      (node (ref "C20") (pin "1") (pinfunction "1_1") (pintype "passive"))
      (node (ref "C21") (pin "2") (pinfunction "2_2") (pintype "passive"))
      (node (ref "C22") (pin "2") (pinfunction "2_2") (pintype "passive"))
      (node (ref "C23") (pin "1") (pinfunction "1_1") (pintype "passive"))
      (node (ref "C24") (pin "1") (pinfunction "1_1") (pintype "passive"))
      (node (ref "C25") (pin "1") (pinfunction "1_1") (pintype "passive"))
      (node (ref "C26") (pin "1") (pinfunction "1_1") (pintype "passive"))
      (node (ref "C27") (pin "1") (pinfunction "1_1") (pintype "passive"))
      (node (ref "C28") (pin "1") (pinfunction "1_1") (pintype "passive"))
      (node (ref "C29") (pin "1") (pinfunction "1_1") (pintype "passive"))
      (node (ref "C30") (pin "1") (pinfunction "1_1") (pintype "passive"))
      (node (ref "D15") (pin "2") (pinfunction "K_2") (pintype "passive"))
      (node (ref "H1") (pin "1") (pinfunction "GND_1") (pintype "passive"))
      (node (ref "P10") (pin "2") (pinfunction "2_2") (pintype "passive"))
      (node (ref "P11") (pin "2") (pinfunction "2_2") (pintype "passive"))
      (node (ref "P12") (pin "3") (pinfunction "3_3") (pintype "passive"))
      (node (ref "P13") (pin "5") (pinfunction "5_5") (pintype "passive"))
      (node (ref "P13") (pin "6") (pinfunction "6_6") (pintype "passive"))
      (node (ref "P2") (pin "2") (pinfunction "GND_2") (pintype "passive"))
      (node (ref "P3") (pin "2") (pinfunction "GND_2") (pintype "passive"))
      (node (ref "P4") (pin "1") (pinfunction "GND_1") (pintype "passive"))
      (node (ref "P5") (pin "1") (pinfunction "GND_1") (pintype "passive"))
      (node (ref "P6") (pin "1") (pinfunction "1_1") (pintype "passive"))
      (node (ref "P7") (pin "1") (pinfunction "1_1") (pintype "passive"))
      (node (ref "P8") (pin "7") (pinfunction "7_7") (pintype "passive"))
      (node (ref "P9") (pin "2") (pinfunction "2_2") (pintype "passive"))
      (node (ref "Pn1") (pin "2") (pinfunction "2_2") (pintype "passive"))
      (node (ref "Q9") (pin "1") (pinfunction "E_1") (pintype "passive"))
      (node (ref "R29") (pin "2") (pinfunction "2_2") (pintype "passive"))
      (node (ref "S3") (pin "1") (pinfunction "1_1") (pintype "passive"))
      (node (ref "S4") (pin "1") (pinfunction "1_1") (pintype "passive"))
      (node (ref "S5") (pin "1") (pinfunction "1_1") (pintype "passive"))
      (node (ref "S6") (pin "1") (pinfunction "1_1") (pintype "passive"))
      (node (ref "S7") (pin "1") (pinfunction "1_1") (pintype "passive"))
      (node (ref "S8") (pin "1") (pinfunction "1_1") (pintype "passive"))
      (node (ref "S9") (pin "1") (pinfunction "1_1") (pintype "passive"))
      (node (ref "S9") (pin "2") (pinfunction "2_2") (pintype "passive"))
      (node (ref "S9") (pin "3") (pinfunction "3_3") (pintype "passive"))
      (node (ref "S9") (pin "4") (pinfunction "4_4") (pintype "passive"))
      (node (ref "U7") (pin "1") (pinfunction "GND_1") (pintype "passive"))
      (node (ref "U7") (pin "72") (pinfunction "GND_72") (pintype "passive"))
    )
    (net (code "62") (name "Net-(D15-A)") (class "Default")
      (node (ref "D15") (pin "1") (pinfunction "A_1") (pintype "passive"))
      (node (ref "R14") (pin "1") (pinfunction "1_1") (pintype "passive"))
    )
    (net (code "63") (name "Net-(D16-A)") (class "Default")
      (node (ref "D16") (pin "1") (pinfunction "A_1") (pintype "passive"))
      (node (ref "R26") (pin "1") (pinfunction "1_1") (pintype "passive"))
    )
    (net (code "64") (name "Net-(D17-A)") (class "Default")
      (node (ref "D17") (pin "1") (pinfunction "A_1") (pintype "passive"))
      (node (ref "R27") (pin "1") (pinfunction "1_1") (pintype "passive"))
    )
    (net (code "65") (name "Net-(D18-A)") (class "Default")
      (node (ref "D18") (pin "1") (pinfunction "A_1") (pintype "passive"))
      (node (ref "R30") (pin "1") (pinfunction "1_1") (pintype "passive"))
    )
    (net (code "66") (name "Net-(D19-A)") (class "Default")
      (node (ref "D19") (pin "1") (pinfunction "A_1") (pintype "passive"))
      (node (ref "R32") (pin "1") (pinfunction "1_1") (pintype "passive"))
    )
    (net (code "67") (name "Net-(H1-7.2V)") (class "Default")
      (node (ref "H1") (pin "2") (pinfunction "7.2V_2") (pintype "passive"))
      (node (ref "S1") (pin "1") (pinfunction "COMMON_1") (pintype "passive"))
    )
    (net (code "68") (name "Net-(Q9-B)") (class "Default")
      (node (ref "Q9") (pin "2") (pinfunction "B_2") (pintype "passive"))
      (node (ref "R21") (pin "2") (pinfunction "2_2") (pintype "passive"))
    )
    (net (code "69") (name "Net-(Q9-C)") (class "Default")
      (node (ref "Q9") (pin "3") (pinfunction "C_3") (pintype "passive"))
      (node (ref "bell1") (pin "2") (pinfunction "B_2") (pintype "passive"))
    )
    (net (code "70") (name "VCC") (class "Default")
      (node (ref "1") (pin "3") (pinfunction "IN_3") (pintype "open_emitter"))
      (node (ref "2") (pin "3") (pinfunction "IN_3") (pintype "open_emitter"))
      (node (ref "3") (pin "3") (pinfunction "IN_3") (pintype "open_emitter"))
      (node (ref "C13") (pin "1") (pinfunction "1_1") (pintype "passive"))
      (node (ref "C15") (pin "2") (pinfunction "2_2") (pintype "passive"))
      (node (ref "C17") (pin "2") (pinfunction "2_2") (pintype "passive"))
      (node (ref "C18") (pin "2") (pinfunction "2_2") (pintype "passive"))
      (node (ref "C21") (pin "1") (pinfunction "1_1") (pintype "passive"))
      (node (ref "C23") (pin "2") (pinfunction "2_2") (pintype "passive"))
      (node (ref "Pn1") (pin "1") (pinfunction "1_1") (pintype "passive"))
      (node (ref "R14") (pin "2") (pinfunction "2_2") (pintype "passive"))
      (node (ref "S1") (pin "2") (pinfunction "NO_2") (pintype "passive"))
      (node (ref "S2") (pin "2") (pinfunction "NO_2") (pintype "passive"))
    )
    (net (code "71") (name "VCC1") (class "Default")
      (node (ref "S2") (pin "1") (pinfunction "COMMON_1") (pintype "passive"))
    )
    (net (code "72") (name "unconnected-(P4-Pad5)") (class "Default")
      (node (ref "P4") (pin "5") (pinfunction "5_5") (pintype "passive"))
    )
    (net (code "73") (name "unconnected-(P4-Pad6)") (class "Default")
      (node (ref "P4") (pin "6") (pinfunction "6_6") (pintype "passive"))
    )
    (net (code "74") (name "unconnected-(P5-Pad5)") (class "Default")
      (node (ref "P5") (pin "5") (pinfunction "5_5") (pintype "passive"))
    )
    (net (code "75") (name "unconnected-(P5-Pad6)") (class "Default")
      (node (ref "P5") (pin "6") (pinfunction "6_6") (pintype "passive"))
    )
    (net (code "76") (name "unconnected-(U7-G0-Pad67)") (class "Default")
      (node (ref "U7") (pin "67") (pinfunction "G0_67") (pintype "passive"))
    )
    (net (code "77") (name "unconnected-(U7-G1-Pad66)") (class "Default")
      (node (ref "U7") (pin "66") (pinfunction "G1_66") (pintype "passive"))
    )
    (net (code "78") (name "unconnected-(U7-G2-Pad65)") (class "Default")
      (node (ref "U7") (pin "65") (pinfunction "G2_65") (pintype "passive"))
    )
    (net (code "79") (name "unconnected-(U7-G3-Pad64)") (class "Default")
      (node (ref "U7") (pin "64") (pinfunction "G3_64") (pintype "passive"))
    )
    (net (code "80") (name "unconnected-(U7-GND-Pad71)") (class "Default")
      (node (ref "U7") (pin "71") (pinfunction "GND_71") (pintype "passive"))
    )
    (net (code "81") (name "unconnected-(U7-I2-Pad61)") (class "Default")
      (node (ref "U7") (pin "61") (pinfunction "I2_61") (pintype "passive"))
    )
    (net (code "82") (name "unconnected-(U7-I3-Pad60)") (class "Default")
      (node (ref "U7") (pin "60") (pinfunction "I3_60") (pintype "passive"))
    )
    (net (code "83") (name "unconnected-(U7-I4-Pad12)") (class "Default")
      (node (ref "U7") (pin "12") (pinfunction "I4_12") (pintype "passive"))
    )
    (net (code "84") (name "unconnected-(U7-I5-Pad27)") (class "Default")
      (node (ref "U7") (pin "27") (pinfunction "I5_27") (pintype "passive"))
    )
    (net (code "85") (name "unconnected-(U7-I6-Pad26)") (class "Default")
      (node (ref "U7") (pin "26") (pinfunction "I6_26") (pintype "passive"))
    )
    (net (code "86") (name "unconnected-(U7-VH-Pad10)") (class "Default")
      (node (ref "U7") (pin "10") (pinfunction "VH_10") (pintype "passive"))
    )
    (net (code "87") (name "unconnected-(U7-VL-Pad11)") (class "Default")
      (node (ref "U7") (pin "11") (pinfunction "VL_11") (pintype "passive"))
    )
  )
)
